# mitosis.net
KiCad netlist of a schematic drawn in Altium Designer
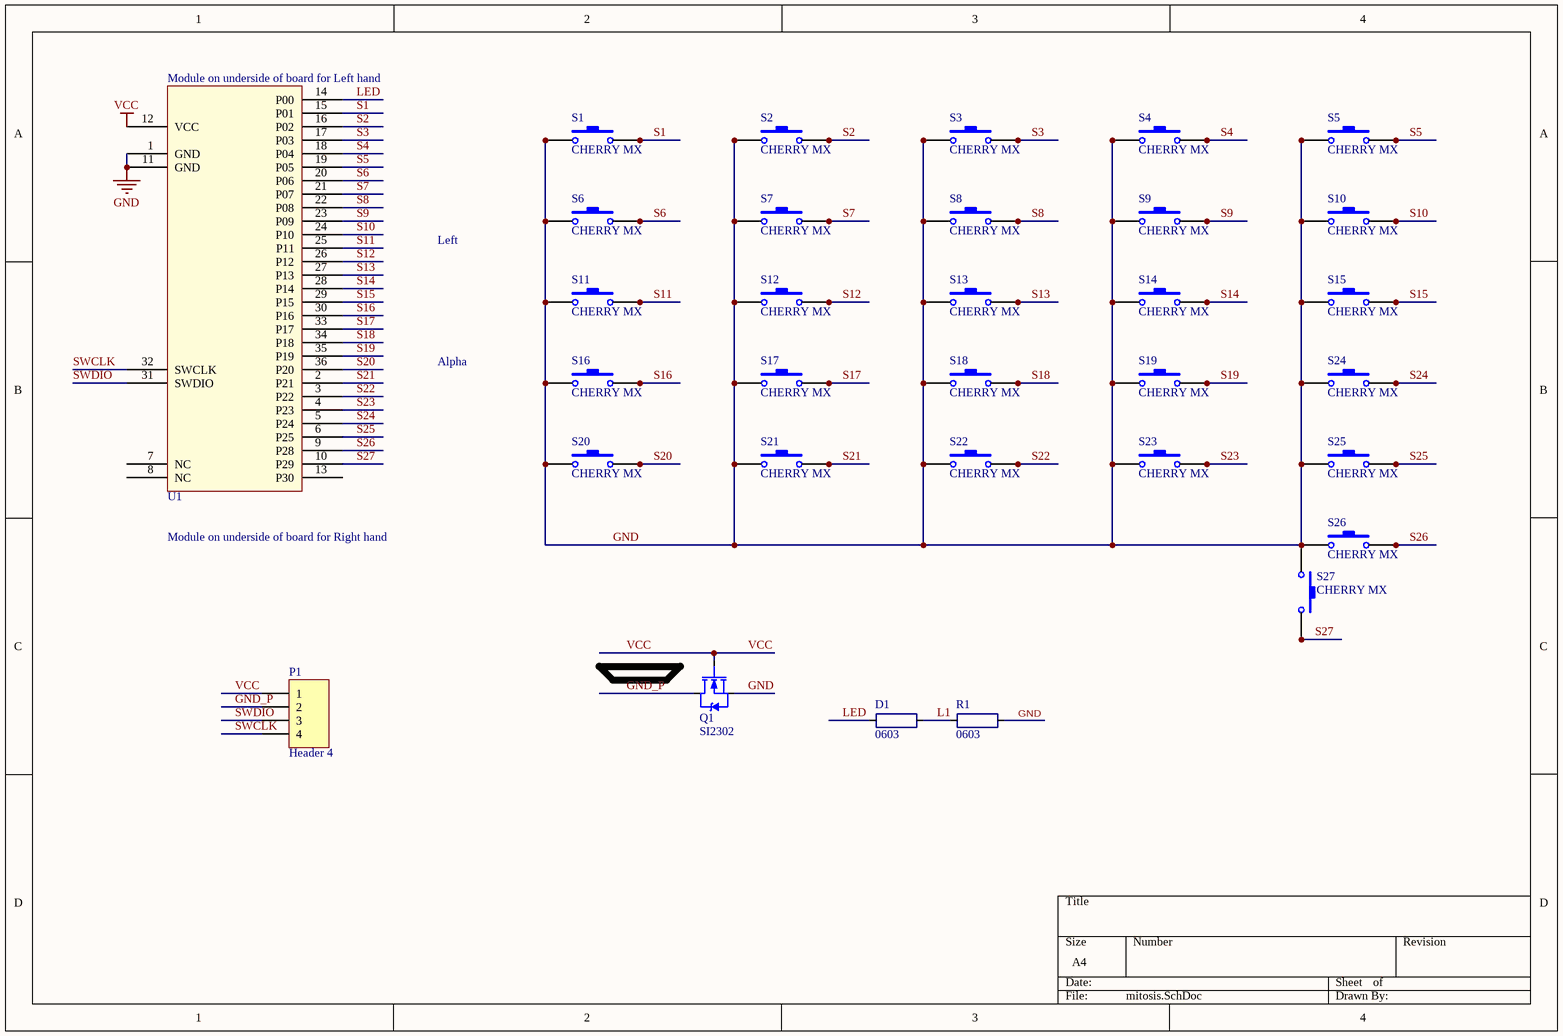
[diagram p0: mitosis.SchDoc]

(export (version "E")
  (design (tool "Eeschema 10.0.6"))
  (components
    (comp (ref "D1") (value "0603") (footprint "RESC2012X06N") (libsource (lib "SK") (part "0603")))
    (comp (ref "P1")
      (value "Header 4")
      (footprint "HDR1X4")
      (description "Header, 4-Pin")
      (fields (field (name "PUBLISHER") "Altium Limited"))
      (libsource (lib "Miscellaneous Connectors") (part "Header 4"))
    )
    (comp (ref "Q1")
      (value "SI2302")
      (footprint "SOT-23")
      (description "N-Channel Logic MOSFET")
      (fields (field (name "PUBLISHER") "Altium Limited"))
      (libsource (lib "SK") (part "SI2302"))
    )
    (comp (ref "R1") (value "0603") (footprint "RESC2012X06N") (libsource (lib "SK") (part "0603")))
    (comp (ref "S1")
      (value "CHERRY MX")
      (footprint "cherry")
      (description "Switch")
      (fields (field (name "PUBLISHER") "Altium Limited"))
      (libsource (lib "SK") (part "CHERRY MX"))
    )
    (comp (ref "S2")
      (value "CHERRY MX")
      (footprint "cherry")
      (description "Switch")
      (fields (field (name "PUBLISHER") "Altium Limited"))
      (libsource (lib "SK") (part "CHERRY MX"))
    )
    (comp (ref "S3")
      (value "CHERRY MX")
      (footprint "cherry")
      (description "Switch")
      (fields (field (name "PUBLISHER") "Altium Limited"))
      (libsource (lib "SK") (part "CHERRY MX"))
    )
    (comp (ref "S4")
      (value "CHERRY MX")
      (footprint "cherry")
      (description "Switch")
      (fields (field (name "PUBLISHER") "Altium Limited"))
      (libsource (lib "SK") (part "CHERRY MX"))
    )
    (comp (ref "S5")
      (value "CHERRY MX")
      (footprint "cherry")
      (description "Switch")
      (fields (field (name "PUBLISHER") "Altium Limited"))
      (libsource (lib "SK") (part "CHERRY MX"))
    )
    (comp (ref "S6")
      (value "CHERRY MX")
      (footprint "cherry")
      (description "Switch")
      (fields (field (name "PUBLISHER") "Altium Limited"))
      (libsource (lib "SK") (part "CHERRY MX"))
    )
    (comp (ref "S7")
      (value "CHERRY MX")
      (footprint "cherry")
      (description "Switch")
      (fields (field (name "PUBLISHER") "Altium Limited"))
      (libsource (lib "SK") (part "CHERRY MX"))
    )
    (comp (ref "S8")
      (value "CHERRY MX")
      (footprint "cherry")
      (description "Switch")
      (fields (field (name "PUBLISHER") "Altium Limited"))
      (libsource (lib "SK") (part "CHERRY MX"))
    )
    (comp (ref "S9")
      (value "CHERRY MX")
      (footprint "cherry")
      (description "Switch")
      (fields (field (name "PUBLISHER") "Altium Limited"))
      (libsource (lib "SK") (part "CHERRY MX"))
    )
    (comp (ref "S10")
      (value "CHERRY MX")
      (footprint "cherry")
      (description "Switch")
      (fields (field (name "PUBLISHER") "Altium Limited"))
      (libsource (lib "SK") (part "CHERRY MX"))
    )
    (comp (ref "S11")
      (value "CHERRY MX")
      (footprint "cherry")
      (description "Switch")
      (fields (field (name "PUBLISHER") "Altium Limited"))
      (libsource (lib "SK") (part "CHERRY MX"))
    )
    (comp (ref "S12")
      (value "CHERRY MX")
      (footprint "cherry")
      (description "Switch")
      (fields (field (name "PUBLISHER") "Altium Limited"))
      (libsource (lib "SK") (part "CHERRY MX"))
    )
    (comp (ref "S13")
      (value "CHERRY MX")
      (footprint "cherry")
      (description "Switch")
      (fields (field (name "PUBLISHER") "Altium Limited"))
      (libsource (lib "SK") (part "CHERRY MX"))
    )
    (comp (ref "S14")
      (value "CHERRY MX")
      (footprint "cherry")
      (description "Switch")
      (fields (field (name "PUBLISHER") "Altium Limited"))
      (libsource (lib "SK") (part "CHERRY MX"))
    )
    (comp (ref "S15")
      (value "CHERRY MX")
      (footprint "cherry")
      (description "Switch")
      (fields (field (name "PUBLISHER") "Altium Limited"))
      (libsource (lib "SK") (part "CHERRY MX"))
    )
    (comp (ref "S16")
      (value "CHERRY MX")
      (footprint "cherry")
      (description "Switch")
      (fields (field (name "PUBLISHER") "Altium Limited"))
      (libsource (lib "SK") (part "CHERRY MX"))
    )
    (comp (ref "S17")
      (value "CHERRY MX")
      (footprint "cherry")
      (description "Switch")
      (fields (field (name "PUBLISHER") "Altium Limited"))
      (libsource (lib "SK") (part "CHERRY MX"))
    )
    (comp (ref "S18")
      (value "CHERRY MX")
      (footprint "cherry")
      (description "Switch")
      (fields (field (name "PUBLISHER") "Altium Limited"))
      (libsource (lib "SK") (part "CHERRY MX"))
    )
    (comp (ref "S19")
      (value "CHERRY MX")
      (footprint "cherry")
      (description "Switch")
      (fields (field (name "PUBLISHER") "Altium Limited"))
      (libsource (lib "SK") (part "CHERRY MX"))
    )
    (comp (ref "S20")
      (value "CHERRY MX")
      (footprint "cherry")
      (description "Switch")
      (fields (field (name "PUBLISHER") "Altium Limited"))
      (libsource (lib "SK") (part "CHERRY MX"))
    )
    (comp (ref "S21")
      (value "CHERRY MX")
      (footprint "cherry")
      (description "Switch")
      (fields (field (name "PUBLISHER") "Altium Limited"))
      (libsource (lib "SK") (part "CHERRY MX"))
    )
    (comp (ref "S22")
      (value "CHERRY MX")
      (footprint "cherry")
      (description "Switch")
      (fields (field (name "PUBLISHER") "Altium Limited"))
      (libsource (lib "SK") (part "CHERRY MX"))
    )
    (comp (ref "S23")
      (value "CHERRY MX")
      (footprint "cherry")
      (description "Switch")
      (fields (field (name "PUBLISHER") "Altium Limited"))
      (libsource (lib "SK") (part "CHERRY MX"))
    )
    (comp (ref "S24")
      (value "CHERRY MX")
      (footprint "cherry")
      (description "Switch")
      (fields (field (name "PUBLISHER") "Altium Limited"))
      (libsource (lib "mitosis") (part "CHERRY MX"))
    )
    (comp (ref "S25")
      (value "CHERRY MX")
      (footprint "cherry")
      (description "Switch")
      (fields (field (name "PUBLISHER") "Altium Limited"))
      (libsource (lib "mitosis") (part "CHERRY MX"))
    )
    (comp (ref "S26")
      (value "CHERRY MX")
      (footprint "cherry")
      (description "Switch")
      (fields (field (name "PUBLISHER") "Altium Limited"))
      (libsource (lib "mitosis") (part "CHERRY MX"))
    )
    (comp (ref "S27")
      (value "CHERRY MX")
      (footprint "cherry")
      (description "Switch")
      (fields (field (name "PUBLISHER") "Altium Limited"))
      (libsource (lib "mitosis") (part "CHERRY MX"))
    )
    (comp (ref "U1")
      (value "Core51822 (B)")
      (footprint "Core51822 (B)")
      (description "NRF51822 (B)")
      (libsource (lib "SK") (part "Core51822 (B)"))
    )
  )
  (nets
    (net (code "1") (name "/GND_P") (class "Default")
      (node (ref "P1") (pin "2") (pinfunction "2_2") (pintype "passive"))
      (node (ref "Q1") (pin "3") (pinfunction "D_3") (pintype "passive"))
    )
    (net (code "2") (name "/L1") (class "Default")
      (node (ref "D1") (pin "1") (pinfunction "1_1") (pintype "passive"))
      (node (ref "R1") (pin "2") (pinfunction "2_2") (pintype "passive"))
    )
    (net (code "3") (name "/LED") (class "Default")
      (node (ref "D1") (pin "2") (pinfunction "2_2") (pintype "passive"))
      (node (ref "U1") (pin "14") (pinfunction "P00_14") (pintype "passive"))
    )
    (net (code "4") (name "/S1") (class "Default")
      (node (ref "S1") (pin "10") (pinfunction "10_10") (pintype "passive"))
      (node (ref "S1") (pin "12") (pinfunction "12_12") (pintype "passive"))
      (node (ref "S1") (pin "2") (pinfunction "2_2") (pintype "passive"))
      (node (ref "S1") (pin "4") (pinfunction "4_4") (pintype "passive"))
      (node (ref "S1") (pin "6") (pinfunction "6_6") (pintype "passive"))
      (node (ref "S1") (pin "8") (pinfunction "8_8") (pintype "passive"))
      (node (ref "U1") (pin "15") (pinfunction "P01_15") (pintype "passive"))
    )
    (net (code "5") (name "/S2") (class "Default")
      (node (ref "S2") (pin "10") (pinfunction "10_10") (pintype "passive"))
      (node (ref "S2") (pin "12") (pinfunction "12_12") (pintype "passive"))
      (node (ref "S2") (pin "2") (pinfunction "2_2") (pintype "passive"))
      (node (ref "S2") (pin "4") (pinfunction "4_4") (pintype "passive"))
      (node (ref "S2") (pin "6") (pinfunction "6_6") (pintype "passive"))
      (node (ref "S2") (pin "8") (pinfunction "8_8") (pintype "passive"))
      (node (ref "U1") (pin "16") (pinfunction "P02_16") (pintype "passive"))
    )
    (net (code "6") (name "/S3") (class "Default")
      (node (ref "S3") (pin "10") (pinfunction "10_10") (pintype "passive"))
      (node (ref "S3") (pin "12") (pinfunction "12_12") (pintype "passive"))
      (node (ref "S3") (pin "2") (pinfunction "2_2") (pintype "passive"))
      (node (ref "S3") (pin "4") (pinfunction "4_4") (pintype "passive"))
      (node (ref "S3") (pin "6") (pinfunction "6_6") (pintype "passive"))
      (node (ref "S3") (pin "8") (pinfunction "8_8") (pintype "passive"))
      (node (ref "U1") (pin "17") (pinfunction "P03_17") (pintype "passive"))
    )
    (net (code "7") (name "/S4") (class "Default")
      (node (ref "S4") (pin "10") (pinfunction "10_10") (pintype "passive"))
      (node (ref "S4") (pin "12") (pinfunction "12_12") (pintype "passive"))
      (node (ref "S4") (pin "2") (pinfunction "2_2") (pintype "passive"))
      (node (ref "S4") (pin "4") (pinfunction "4_4") (pintype "passive"))
      (node (ref "S4") (pin "6") (pinfunction "6_6") (pintype "passive"))
      (node (ref "S4") (pin "8") (pinfunction "8_8") (pintype "passive"))
      (node (ref "U1") (pin "18") (pinfunction "P04_18") (pintype "passive"))
    )
    (net (code "8") (name "/S5") (class "Default")
      (node (ref "S5") (pin "10") (pinfunction "10_10") (pintype "passive"))
      (node (ref "S5") (pin "12") (pinfunction "12_12") (pintype "passive"))
      (node (ref "S5") (pin "2") (pinfunction "2_2") (pintype "passive"))
      (node (ref "S5") (pin "4") (pinfunction "4_4") (pintype "passive"))
      (node (ref "S5") (pin "6") (pinfunction "6_6") (pintype "passive"))
      (node (ref "S5") (pin "8") (pinfunction "8_8") (pintype "passive"))
      (node (ref "U1") (pin "19") (pinfunction "P05_19") (pintype "passive"))
    )
    (net (code "9") (name "/S6") (class "Default")
      (node (ref "S6") (pin "10") (pinfunction "10_10") (pintype "passive"))
      (node (ref "S6") (pin "12") (pinfunction "12_12") (pintype "passive"))
      (node (ref "S6") (pin "2") (pinfunction "2_2") (pintype "passive"))
      (node (ref "S6") (pin "4") (pinfunction "4_4") (pintype "passive"))
      (node (ref "S6") (pin "6") (pinfunction "6_6") (pintype "passive"))
      (node (ref "S6") (pin "8") (pinfunction "8_8") (pintype "passive"))
      (node (ref "U1") (pin "20") (pinfunction "P06_20") (pintype "passive"))
    )
    (net (code "10") (name "/S7") (class "Default")
      (node (ref "S7") (pin "10") (pinfunction "10_10") (pintype "passive"))
      (node (ref "S7") (pin "12") (pinfunction "12_12") (pintype "passive"))
      (node (ref "S7") (pin "2") (pinfunction "2_2") (pintype "passive"))
      (node (ref "S7") (pin "4") (pinfunction "4_4") (pintype "passive"))
      (node (ref "S7") (pin "6") (pinfunction "6_6") (pintype "passive"))
      (node (ref "S7") (pin "8") (pinfunction "8_8") (pintype "passive"))
      (node (ref "U1") (pin "21") (pinfunction "P07_21") (pintype "passive"))
    )
    (net (code "11") (name "/S8") (class "Default")
      (node (ref "S8") (pin "10") (pinfunction "10_10") (pintype "passive"))
      (node (ref "S8") (pin "12") (pinfunction "12_12") (pintype "passive"))
      (node (ref "S8") (pin "2") (pinfunction "2_2") (pintype "passive"))
      (node (ref "S8") (pin "4") (pinfunction "4_4") (pintype "passive"))
      (node (ref "S8") (pin "6") (pinfunction "6_6") (pintype "passive"))
      (node (ref "S8") (pin "8") (pinfunction "8_8") (pintype "passive"))
      (node (ref "U1") (pin "22") (pinfunction "P08_22") (pintype "passive"))
    )
    (net (code "12") (name "/S9") (class "Default")
      (node (ref "S9") (pin "10") (pinfunction "10_10") (pintype "passive"))
      (node (ref "S9") (pin "12") (pinfunction "12_12") (pintype "passive"))
      (node (ref "S9") (pin "2") (pinfunction "2_2") (pintype "passive"))
      (node (ref "S9") (pin "4") (pinfunction "4_4") (pintype "passive"))
      (node (ref "S9") (pin "6") (pinfunction "6_6") (pintype "passive"))
      (node (ref "S9") (pin "8") (pinfunction "8_8") (pintype "passive"))
      (node (ref "U1") (pin "23") (pinfunction "P09_23") (pintype "passive"))
    )
    (net (code "13") (name "/S10") (class "Default")
      (node (ref "S10") (pin "10") (pinfunction "10_10") (pintype "passive"))
      (node (ref "S10") (pin "12") (pinfunction "12_12") (pintype "passive"))
      (node (ref "S10") (pin "2") (pinfunction "2_2") (pintype "passive"))
      (node (ref "S10") (pin "4") (pinfunction "4_4") (pintype "passive"))
      (node (ref "S10") (pin "6") (pinfunction "6_6") (pintype "passive"))
      (node (ref "S10") (pin "8") (pinfunction "8_8") (pintype "passive"))
      (node (ref "U1") (pin "24") (pinfunction "P10_24") (pintype "passive"))
    )
    (net (code "14") (name "/S11") (class "Default")
      (node (ref "S11") (pin "10") (pinfunction "10_10") (pintype "passive"))
      (node (ref "S11") (pin "12") (pinfunction "12_12") (pintype "passive"))
      (node (ref "S11") (pin "2") (pinfunction "2_2") (pintype "passive"))
      (node (ref "S11") (pin "4") (pinfunction "4_4") (pintype "passive"))
      (node (ref "S11") (pin "6") (pinfunction "6_6") (pintype "passive"))
      (node (ref "S11") (pin "8") (pinfunction "8_8") (pintype "passive"))
      (node (ref "U1") (pin "25") (pinfunction "P11_25") (pintype "passive"))
    )
    (net (code "15") (name "/S12") (class "Default")
      (node (ref "S12") (pin "10") (pinfunction "10_10") (pintype "passive"))
      (node (ref "S12") (pin "12") (pinfunction "12_12") (pintype "passive"))
      (node (ref "S12") (pin "2") (pinfunction "2_2") (pintype "passive"))
      (node (ref "S12") (pin "4") (pinfunction "4_4") (pintype "passive"))
      (node (ref "S12") (pin "6") (pinfunction "6_6") (pintype "passive"))
      (node (ref "S12") (pin "8") (pinfunction "8_8") (pintype "passive"))
      (node (ref "U1") (pin "26") (pinfunction "P12_26") (pintype "passive"))
    )
    (net (code "16") (name "/S13") (class "Default")
      (node (ref "S13") (pin "10") (pinfunction "10_10") (pintype "passive"))
      (node (ref "S13") (pin "12") (pinfunction "12_12") (pintype "passive"))
      (node (ref "S13") (pin "2") (pinfunction "2_2") (pintype "passive"))
      (node (ref "S13") (pin "4") (pinfunction "4_4") (pintype "passive"))
      (node (ref "S13") (pin "6") (pinfunction "6_6") (pintype "passive"))
      (node (ref "S13") (pin "8") (pinfunction "8_8") (pintype "passive"))
      (node (ref "U1") (pin "27") (pinfunction "P13_27") (pintype "passive"))
    )
    (net (code "17") (name "/S14") (class "Default")
      (node (ref "S14") (pin "10") (pinfunction "10_10") (pintype "passive"))
      (node (ref "S14") (pin "12") (pinfunction "12_12") (pintype "passive"))
      (node (ref "S14") (pin "2") (pinfunction "2_2") (pintype "passive"))
      (node (ref "S14") (pin "4") (pinfunction "4_4") (pintype "passive"))
      (node (ref "S14") (pin "6") (pinfunction "6_6") (pintype "passive"))
      (node (ref "S14") (pin "8") (pinfunction "8_8") (pintype "passive"))
      (node (ref "U1") (pin "28") (pinfunction "P14_28") (pintype "passive"))
    )
    (net (code "18") (name "/S15") (class "Default")
      (node (ref "S15") (pin "10") (pinfunction "10_10") (pintype "passive"))
      (node (ref "S15") (pin "12") (pinfunction "12_12") (pintype "passive"))
      (node (ref "S15") (pin "2") (pinfunction "2_2") (pintype "passive"))
      (node (ref "S15") (pin "4") (pinfunction "4_4") (pintype "passive"))
      (node (ref "S15") (pin "6") (pinfunction "6_6") (pintype "passive"))
      (node (ref "S15") (pin "8") (pinfunction "8_8") (pintype "passive"))
      (node (ref "U1") (pin "29") (pinfunction "P15_29") (pintype "passive"))
    )
    (net (code "19") (name "/S16") (class "Default")
      (node (ref "S16") (pin "10") (pinfunction "10_10") (pintype "passive"))
      (node (ref "S16") (pin "12") (pinfunction "12_12") (pintype "passive"))
      (node (ref "S16") (pin "2") (pinfunction "2_2") (pintype "passive"))
      (node (ref "S16") (pin "4") (pinfunction "4_4") (pintype "passive"))
      (node (ref "S16") (pin "6") (pinfunction "6_6") (pintype "passive"))
      (node (ref "S16") (pin "8") (pinfunction "8_8") (pintype "passive"))
      (node (ref "U1") (pin "30") (pinfunction "P16_30") (pintype "passive"))
    )
    (net (code "20") (name "/S17") (class "Default")
      (node (ref "S17") (pin "10") (pinfunction "10_10") (pintype "passive"))
      (node (ref "S17") (pin "12") (pinfunction "12_12") (pintype "passive"))
      (node (ref "S17") (pin "2") (pinfunction "2_2") (pintype "passive"))
      (node (ref "S17") (pin "4") (pinfunction "4_4") (pintype "passive"))
      (node (ref "S17") (pin "6") (pinfunction "6_6") (pintype "passive"))
      (node (ref "S17") (pin "8") (pinfunction "8_8") (pintype "passive"))
      (node (ref "U1") (pin "33") (pinfunction "P17_33") (pintype "passive"))
    )
    (net (code "21") (name "/S18") (class "Default")
      (node (ref "S18") (pin "10") (pinfunction "10_10") (pintype "passive"))
      (node (ref "S18") (pin "12") (pinfunction "12_12") (pintype "passive"))
      (node (ref "S18") (pin "2") (pinfunction "2_2") (pintype "passive"))
      (node (ref "S18") (pin "4") (pinfunction "4_4") (pintype "passive"))
      (node (ref "S18") (pin "6") (pinfunction "6_6") (pintype "passive"))
      (node (ref "S18") (pin "8") (pinfunction "8_8") (pintype "passive"))
      (node (ref "U1") (pin "34") (pinfunction "P18_34") (pintype "passive"))
    )
    (net (code "22") (name "/S19") (class "Default")
      (node (ref "S19") (pin "10") (pinfunction "10_10") (pintype "passive"))
      (node (ref "S19") (pin "12") (pinfunction "12_12") (pintype "passive"))
      (node (ref "S19") (pin "2") (pinfunction "2_2") (pintype "passive"))
      (node (ref "S19") (pin "4") (pinfunction "4_4") (pintype "passive"))
      (node (ref "S19") (pin "6") (pinfunction "6_6") (pintype "passive"))
      (node (ref "S19") (pin "8") (pinfunction "8_8") (pintype "passive"))
      (node (ref "U1") (pin "35") (pinfunction "P19_35") (pintype "passive"))
    )
    (net (code "23") (name "/S20") (class "Default")
      (node (ref "S20") (pin "10") (pinfunction "10_10") (pintype "passive"))
      (node (ref "S20") (pin "12") (pinfunction "12_12") (pintype "passive"))
      (node (ref "S20") (pin "2") (pinfunction "2_2") (pintype "passive"))
      (node (ref "S20") (pin "4") (pinfunction "4_4") (pintype "passive"))
      (node (ref "S20") (pin "6") (pinfunction "6_6") (pintype "passive"))
      (node (ref "S20") (pin "8") (pinfunction "8_8") (pintype "passive"))
      (node (ref "U1") (pin "36") (pinfunction "P20_36") (pintype "passive"))
    )
    (net (code "24") (name "/S21") (class "Default")
      (node (ref "S21") (pin "10") (pinfunction "10_10") (pintype "passive"))
      (node (ref "S21") (pin "12") (pinfunction "12_12") (pintype "passive"))
      (node (ref "S21") (pin "2") (pinfunction "2_2") (pintype "passive"))
      (node (ref "S21") (pin "4") (pinfunction "4_4") (pintype "passive"))
      (node (ref "S21") (pin "6") (pinfunction "6_6") (pintype "passive"))
      (node (ref "S21") (pin "8") (pinfunction "8_8") (pintype "passive"))
      (node (ref "U1") (pin "2") (pinfunction "P21_2") (pintype "passive"))
    )
    (net (code "25") (name "/S22") (class "Default")
      (node (ref "S22") (pin "10") (pinfunction "10_10") (pintype "passive"))
      (node (ref "S22") (pin "12") (pinfunction "12_12") (pintype "passive"))
      (node (ref "S22") (pin "2") (pinfunction "2_2") (pintype "passive"))
      (node (ref "S22") (pin "4") (pinfunction "4_4") (pintype "passive"))
      (node (ref "S22") (pin "6") (pinfunction "6_6") (pintype "passive"))
      (node (ref "S22") (pin "8") (pinfunction "8_8") (pintype "passive"))
      (node (ref "U1") (pin "3") (pinfunction "P22_3") (pintype "passive"))
    )
    (net (code "26") (name "/S23") (class "Default")
      (node (ref "S23") (pin "10") (pinfunction "10_10") (pintype "passive"))
      (node (ref "S23") (pin "12") (pinfunction "12_12") (pintype "passive"))
      (node (ref "S23") (pin "2") (pinfunction "2_2") (pintype "passive"))
      (node (ref "S23") (pin "4") (pinfunction "4_4") (pintype "passive"))
      (node (ref "S23") (pin "6") (pinfunction "6_6") (pintype "passive"))
      (node (ref "S23") (pin "8") (pinfunction "8_8") (pintype "passive"))
      (node (ref "U1") (pin "4") (pinfunction "P23_4") (pintype "passive"))
    )
    (net (code "27") (name "/S24") (class "Default")
      (node (ref "S24") (pin "10") (pinfunction "10_10") (pintype "passive"))
      (node (ref "S24") (pin "12") (pinfunction "12_12") (pintype "passive"))
      (node (ref "S24") (pin "2") (pinfunction "2_2") (pintype "passive"))
      (node (ref "S24") (pin "4") (pinfunction "4_4") (pintype "passive"))
      (node (ref "S24") (pin "6") (pinfunction "6_6") (pintype "passive"))
      (node (ref "S24") (pin "8") (pinfunction "8_8") (pintype "passive"))
      (node (ref "U1") (pin "5") (pinfunction "P24_5") (pintype "passive"))
    )
    (net (code "28") (name "/S25") (class "Default")
      (node (ref "S25") (pin "10") (pinfunction "10_10") (pintype "passive"))
      (node (ref "S25") (pin "12") (pinfunction "12_12") (pintype "passive"))
      (node (ref "S25") (pin "2") (pinfunction "2_2") (pintype "passive"))
      (node (ref "S25") (pin "4") (pinfunction "4_4") (pintype "passive"))
      (node (ref "S25") (pin "6") (pinfunction "6_6") (pintype "passive"))
      (node (ref "S25") (pin "8") (pinfunction "8_8") (pintype "passive"))
      (node (ref "U1") (pin "6") (pinfunction "P25_6") (pintype "passive"))
    )
    (net (code "29") (name "/S26") (class "Default")
      (node (ref "S26") (pin "10") (pinfunction "10_10") (pintype "passive"))
      (node (ref "S26") (pin "12") (pinfunction "12_12") (pintype "passive"))
      (node (ref "S26") (pin "2") (pinfunction "2_2") (pintype "passive"))
      (node (ref "S26") (pin "4") (pinfunction "4_4") (pintype "passive"))
      (node (ref "S26") (pin "6") (pinfunction "6_6") (pintype "passive"))
      (node (ref "S26") (pin "8") (pinfunction "8_8") (pintype "passive"))
      (node (ref "U1") (pin "9") (pinfunction "P28_9") (pintype "passive"))
    )
    (net (code "30") (name "/S27") (class "Default")
      (node (ref "S27") (pin "10") (pinfunction "10_10") (pintype "passive"))
      (node (ref "S27") (pin "12") (pinfunction "12_12") (pintype "passive"))
      (node (ref "S27") (pin "2") (pinfunction "2_2") (pintype "passive"))
      (node (ref "S27") (pin "4") (pinfunction "4_4") (pintype "passive"))
      (node (ref "S27") (pin "6") (pinfunction "6_6") (pintype "passive"))
      (node (ref "S27") (pin "8") (pinfunction "8_8") (pintype "passive"))
      (node (ref "U1") (pin "10") (pinfunction "P29_10") (pintype "passive"))
    )
    (net (code "31") (name "/SWCLK") (class "Default")
      (node (ref "P1") (pin "4") (pinfunction "4_4") (pintype "passive"))
      (node (ref "U1") (pin "32") (pinfunction "SWCLK_32") (pintype "passive"))
    )
    (net (code "32") (name "/SWDIO") (class "Default")
      (node (ref "P1") (pin "3") (pinfunction "3_3") (pintype "passive"))
      (node (ref "U1") (pin "31") (pinfunction "SWDIO_31") (pintype "passive"))
    )
    (net (code "33") (name "GND") (class "Default")
      (node (ref "Q1") (pin "2") (pinfunction "S_2") (pintype "passive"))
      (node (ref "R1") (pin "1") (pinfunction "1_1") (pintype "passive"))
      (node (ref "S1") (pin "1") (pinfunction "1_1") (pintype "passive"))
      (node (ref "S1") (pin "11") (pinfunction "11_11") (pintype "passive"))
      (node (ref "S1") (pin "3") (pinfunction "3_3") (pintype "passive"))
      (node (ref "S1") (pin "5") (pinfunction "5_5") (pintype "passive"))
      (node (ref "S1") (pin "7") (pinfunction "7_7") (pintype "passive"))
      (node (ref "S1") (pin "9") (pinfunction "9_9") (pintype "passive"))
      (node (ref "S10") (pin "1") (pinfunction "1_1") (pintype "passive"))
      (node (ref "S10") (pin "11") (pinfunction "11_11") (pintype "passive"))
      (node (ref "S10") (pin "3") (pinfunction "3_3") (pintype "passive"))
      (node (ref "S10") (pin "5") (pinfunction "5_5") (pintype "passive"))
      (node (ref "S10") (pin "7") (pinfunction "7_7") (pintype "passive"))
      (node (ref "S10") (pin "9") (pinfunction "9_9") (pintype "passive"))
      (node (ref "S11") (pin "1") (pinfunction "1_1") (pintype "passive"))
      (node (ref "S11") (pin "11") (pinfunction "11_11") (pintype "passive"))
      (node (ref "S11") (pin "3") (pinfunction "3_3") (pintype "passive"))
      (node (ref "S11") (pin "5") (pinfunction "5_5") (pintype "passive"))
      (node (ref "S11") (pin "7") (pinfunction "7_7") (pintype "passive"))
      (node (ref "S11") (pin "9") (pinfunction "9_9") (pintype "passive"))
      (node (ref "S12") (pin "1") (pinfunction "1_1") (pintype "passive"))
      (node (ref "S12") (pin "11") (pinfunction "11_11") (pintype "passive"))
      (node (ref "S12") (pin "3") (pinfunction "3_3") (pintype "passive"))
      (node (ref "S12") (pin "5") (pinfunction "5_5") (pintype "passive"))
      (node (ref "S12") (pin "7") (pinfunction "7_7") (pintype "passive"))
      (node (ref "S12") (pin "9") (pinfunction "9_9") (pintype "passive"))
      (node (ref "S13") (pin "1") (pinfunction "1_1") (pintype "passive"))
      (node (ref "S13") (pin "11") (pinfunction "11_11") (pintype "passive"))
      (node (ref "S13") (pin "3") (pinfunction "3_3") (pintype "passive"))
      (node (ref "S13") (pin "5") (pinfunction "5_5") (pintype "passive"))
      (node (ref "S13") (pin "7") (pinfunction "7_7") (pintype "passive"))
      (node (ref "S13") (pin "9") (pinfunction "9_9") (pintype "passive"))
      (node (ref "S14") (pin "1") (pinfunction "1_1") (pintype "passive"))
      (node (ref "S14") (pin "11") (pinfunction "11_11") (pintype "passive"))
      (node (ref "S14") (pin "3") (pinfunction "3_3") (pintype "passive"))
      (node (ref "S14") (pin "5") (pinfunction "5_5") (pintype "passive"))
      (node (ref "S14") (pin "7") (pinfunction "7_7") (pintype "passive"))
      (node (ref "S14") (pin "9") (pinfunction "9_9") (pintype "passive"))
      (node (ref "S15") (pin "1") (pinfunction "1_1") (pintype "passive"))
      (node (ref "S15") (pin "11") (pinfunction "11_11") (pintype "passive"))
      (node (ref "S15") (pin "3") (pinfunction "3_3") (pintype "passive"))
      (node (ref "S15") (pin "5") (pinfunction "5_5") (pintype "passive"))
      (node (ref "S15") (pin "7") (pinfunction "7_7") (pintype "passive"))
      (node (ref "S15") (pin "9") (pinfunction "9_9") (pintype "passive"))
      (node (ref "S16") (pin "1") (pinfunction "1_1") (pintype "passive"))
      (node (ref "S16") (pin "11") (pinfunction "11_11") (pintype "passive"))
      (node (ref "S16") (pin "3") (pinfunction "3_3") (pintype "passive"))
      (node (ref "S16") (pin "5") (pinfunction "5_5") (pintype "passive"))
      (node (ref "S16") (pin "7") (pinfunction "7_7") (pintype "passive"))
      (node (ref "S16") (pin "9") (pinfunction "9_9") (pintype "passive"))
      (node (ref "S17") (pin "1") (pinfunction "1_1") (pintype "passive"))
      (node (ref "S17") (pin "11") (pinfunction "11_11") (pintype "passive"))
      (node (ref "S17") (pin "3") (pinfunction "3_3") (pintype "passive"))
      (node (ref "S17") (pin "5") (pinfunction "5_5") (pintype "passive"))
      (node (ref "S17") (pin "7") (pinfunction "7_7") (pintype "passive"))
      (node (ref "S17") (pin "9") (pinfunction "9_9") (pintype "passive"))
      (node (ref "S18") (pin "1") (pinfunction "1_1") (pintype "passive"))
      (node (ref "S18") (pin "11") (pinfunction "11_11") (pintype "passive"))
      (node (ref "S18") (pin "3") (pinfunction "3_3") (pintype "passive"))
      (node (ref "S18") (pin "5") (pinfunction "5_5") (pintype "passive"))
      (node (ref "S18") (pin "7") (pinfunction "7_7") (pintype "passive"))
      (node (ref "S18") (pin "9") (pinfunction "9_9") (pintype "passive"))
      (node (ref "S19") (pin "1") (pinfunction "1_1") (pintype "passive"))
      (node (ref "S19") (pin "11") (pinfunction "11_11") (pintype "passive"))
      (node (ref "S19") (pin "3") (pinfunction "3_3") (pintype "passive"))
      (node (ref "S19") (pin "5") (pinfunction "5_5") (pintype "passive"))
      (node (ref "S19") (pin "7") (pinfunction "7_7") (pintype "passive"))
      (node (ref "S19") (pin "9") (pinfunction "9_9") (pintype "passive"))
      (node (ref "S2") (pin "1") (pinfunction "1_1") (pintype "passive"))
      (node (ref "S2") (pin "11") (pinfunction "11_11") (pintype "passive"))
      (node (ref "S2") (pin "3") (pinfunction "3_3") (pintype "passive"))
      (node (ref "S2") (pin "5") (pinfunction "5_5") (pintype "passive"))
      (node (ref "S2") (pin "7") (pinfunction "7_7") (pintype "passive"))
      (node (ref "S2") (pin "9") (pinfunction "9_9") (pintype "passive"))
      (node (ref "S20") (pin "1") (pinfunction "1_1") (pintype "passive"))
      (node (ref "S20") (pin "11") (pinfunction "11_11") (pintype "passive"))
      (node (ref "S20") (pin "3") (pinfunction "3_3") (pintype "passive"))
      (node (ref "S20") (pin "5") (pinfunction "5_5") (pintype "passive"))
      (node (ref "S20") (pin "7") (pinfunction "7_7") (pintype "passive"))
      (node (ref "S20") (pin "9") (pinfunction "9_9") (pintype "passive"))
      (node (ref "S21") (pin "1") (pinfunction "1_1") (pintype "passive"))
      (node (ref "S21") (pin "11") (pinfunction "11_11") (pintype "passive"))
      (node (ref "S21") (pin "3") (pinfunction "3_3") (pintype "passive"))
      (node (ref "S21") (pin "5") (pinfunction "5_5") (pintype "passive"))
      (node (ref "S21") (pin "7") (pinfunction "7_7") (pintype "passive"))
      (node (ref "S21") (pin "9") (pinfunction "9_9") (pintype "passive"))
      (node (ref "S22") (pin "1") (pinfunction "1_1") (pintype "passive"))
      (node (ref "S22") (pin "11") (pinfunction "11_11") (pintype "passive"))
      (node (ref "S22") (pin "3") (pinfunction "3_3") (pintype "passive"))
      (node (ref "S22") (pin "5") (pinfunction "5_5") (pintype "passive"))
      (node (ref "S22") (pin "7") (pinfunction "7_7") (pintype "passive"))
      (node (ref "S22") (pin "9") (pinfunction "9_9") (pintype "passive"))
      (node (ref "S23") (pin "1") (pinfunction "1_1") (pintype "passive"))
      (node (ref "S23") (pin "11") (pinfunction "11_11") (pintype "passive"))
      (node (ref "S23") (pin "3") (pinfunction "3_3") (pintype "passive"))
      (node (ref "S23") (pin "5") (pinfunction "5_5") (pintype "passive"))
      (node (ref "S23") (pin "7") (pinfunction "7_7") (pintype "passive"))
      (node (ref "S23") (pin "9") (pinfunction "9_9") (pintype "passive"))
      (node (ref "S24") (pin "1") (pinfunction "1_1") (pintype "passive"))
      (node (ref "S24") (pin "11") (pinfunction "11_11") (pintype "passive"))
      (node (ref "S24") (pin "3") (pinfunction "3_3") (pintype "passive"))
      (node (ref "S24") (pin "5") (pinfunction "5_5") (pintype "passive"))
      (node (ref "S24") (pin "7") (pinfunction "7_7") (pintype "passive"))
      (node (ref "S24") (pin "9") (pinfunction "9_9") (pintype "passive"))
      (node (ref "S25") (pin "1") (pinfunction "1_1") (pintype "passive"))
      (node (ref "S25") (pin "11") (pinfunction "11_11") (pintype "passive"))
      (node (ref "S25") (pin "3") (pinfunction "3_3") (pintype "passive"))
      (node (ref "S25") (pin "5") (pinfunction "5_5") (pintype "passive"))
      (node (ref "S25") (pin "7") (pinfunction "7_7") (pintype "passive"))
      (node (ref "S25") (pin "9") (pinfunction "9_9") (pintype "passive"))
      (node (ref "S26") (pin "1") (pinfunction "1_1") (pintype "passive"))
      (node (ref "S26") (pin "11") (pinfunction "11_11") (pintype "passive"))
      (node (ref "S26") (pin "3") (pinfunction "3_3") (pintype "passive"))
      (node (ref "S26") (pin "5") (pinfunction "5_5") (pintype "passive"))
      (node (ref "S26") (pin "7") (pinfunction "7_7") (pintype "passive"))
      (node (ref "S26") (pin "9") (pinfunction "9_9") (pintype "passive"))
      (node (ref "S27") (pin "1") (pinfunction "1_1") (pintype "passive"))
      (node (ref "S27") (pin "11") (pinfunction "11_11") (pintype "passive"))
      (node (ref "S27") (pin "3") (pinfunction "3_3") (pintype "passive"))
      (node (ref "S27") (pin "5") (pinfunction "5_5") (pintype "passive"))
      (node (ref "S27") (pin "7") (pinfunction "7_7") (pintype "passive"))
      (node (ref "S27") (pin "9") (pinfunction "9_9") (pintype "passive"))
      (node (ref "S3") (pin "1") (pinfunction "1_1") (pintype "passive"))
      (node (ref "S3") (pin "11") (pinfunction "11_11") (pintype "passive"))
      (node (ref "S3") (pin "3") (pinfunction "3_3") (pintype "passive"))
      (node (ref "S3") (pin "5") (pinfunction "5_5") (pintype "passive"))
      (node (ref "S3") (pin "7") (pinfunction "7_7") (pintype "passive"))
      (node (ref "S3") (pin "9") (pinfunction "9_9") (pintype "passive"))
      (node (ref "S4") (pin "1") (pinfunction "1_1") (pintype "passive"))
      (node (ref "S4") (pin "11") (pinfunction "11_11") (pintype "passive"))
      (node (ref "S4") (pin "3") (pinfunction "3_3") (pintype "passive"))
      (node (ref "S4") (pin "5") (pinfunction "5_5") (pintype "passive"))
      (node (ref "S4") (pin "7") (pinfunction "7_7") (pintype "passive"))
      (node (ref "S4") (pin "9") (pinfunction "9_9") (pintype "passive"))
      (node (ref "S5") (pin "1") (pinfunction "1_1") (pintype "passive"))
      (node (ref "S5") (pin "11") (pinfunction "11_11") (pintype "passive"))
      (node (ref "S5") (pin "3") (pinfunction "3_3") (pintype "passive"))
      (node (ref "S5") (pin "5") (pinfunction "5_5") (pintype "passive"))
      (node (ref "S5") (pin "7") (pinfunction "7_7") (pintype "passive"))
      (node (ref "S5") (pin "9") (pinfunction "9_9") (pintype "passive"))
      (node (ref "S6") (pin "1") (pinfunction "1_1") (pintype "passive"))
      (node (ref "S6") (pin "11") (pinfunction "11_11") (pintype "passive"))
      (node (ref "S6") (pin "3") (pinfunction "3_3") (pintype "passive"))
      (node (ref "S6") (pin "5") (pinfunction "5_5") (pintype "passive"))
      (node (ref "S6") (pin "7") (pinfunction "7_7") (pintype "passive"))
      (node (ref "S6") (pin "9") (pinfunction "9_9") (pintype "passive"))
      (node (ref "S7") (pin "1") (pinfunction "1_1") (pintype "passive"))
      (node (ref "S7") (pin "11") (pinfunction "11_11") (pintype "passive"))
      (node (ref "S7") (pin "3") (pinfunction "3_3") (pintype "passive"))
      (node (ref "S7") (pin "5") (pinfunction "5_5") (pintype "passive"))
      (node (ref "S7") (pin "7") (pinfunction "7_7") (pintype "passive"))
      (node (ref "S7") (pin "9") (pinfunction "9_9") (pintype "passive"))
      (node (ref "S8") (pin "1") (pinfunction "1_1") (pintype "passive"))
      (node (ref "S8") (pin "11") (pinfunction "11_11") (pintype "passive"))
      (node (ref "S8") (pin "3") (pinfunction "3_3") (pintype "passive"))
      (node (ref "S8") (pin "5") (pinfunction "5_5") (pintype "passive"))
      (node (ref "S8") (pin "7") (pinfunction "7_7") (pintype "passive"))
      (node (ref "S8") (pin "9") (pinfunction "9_9") (pintype "passive"))
      (node (ref "S9") (pin "1") (pinfunction "1_1") (pintype "passive"))
      (node (ref "S9") (pin "11") (pinfunction "11_11") (pintype "passive"))
      (node (ref "S9") (pin "3") (pinfunction "3_3") (pintype "passive"))
      (node (ref "S9") (pin "5") (pinfunction "5_5") (pintype "passive"))
      (node (ref "S9") (pin "7") (pinfunction "7_7") (pintype "passive"))
      (node (ref "S9") (pin "9") (pinfunction "9_9") (pintype "passive"))
      (node (ref "U1") (pin "1") (pinfunction "GND_1") (pintype "passive"))
      (node (ref "U1") (pin "11") (pinfunction "GND_11") (pintype "passive"))
    )
    (net (code "34") (name "VCC") (class "Default")
      (node (ref "P1") (pin "1") (pinfunction "1_1") (pintype "passive"))
      (node (ref "Q1") (pin "1") (pinfunction "G_1") (pintype "passive"))
      (node (ref "U1") (pin "12") (pinfunction "VCC_12") (pintype "passive"))
    )
    (net (code "35") (name "unconnected-(U1-NC-Pad7)") (class "Default")
      (node (ref "U1") (pin "7") (pinfunction "NC_7") (pintype "passive"))
    )
    (net (code "36") (name "unconnected-(U1-NC-Pad8)") (class "Default")
      (node (ref "U1") (pin "8") (pinfunction "NC_8") (pintype "passive"))
    )
    (net (code "37") (name "unconnected-(U1-P30-Pad13)") (class "Default")
      (node (ref "U1") (pin "13") (pinfunction "P30_13") (pintype "passive"))
    )
  )
)
